# front_end_test_harness.net
KiCad netlist of a schematic drawn in EAGLE
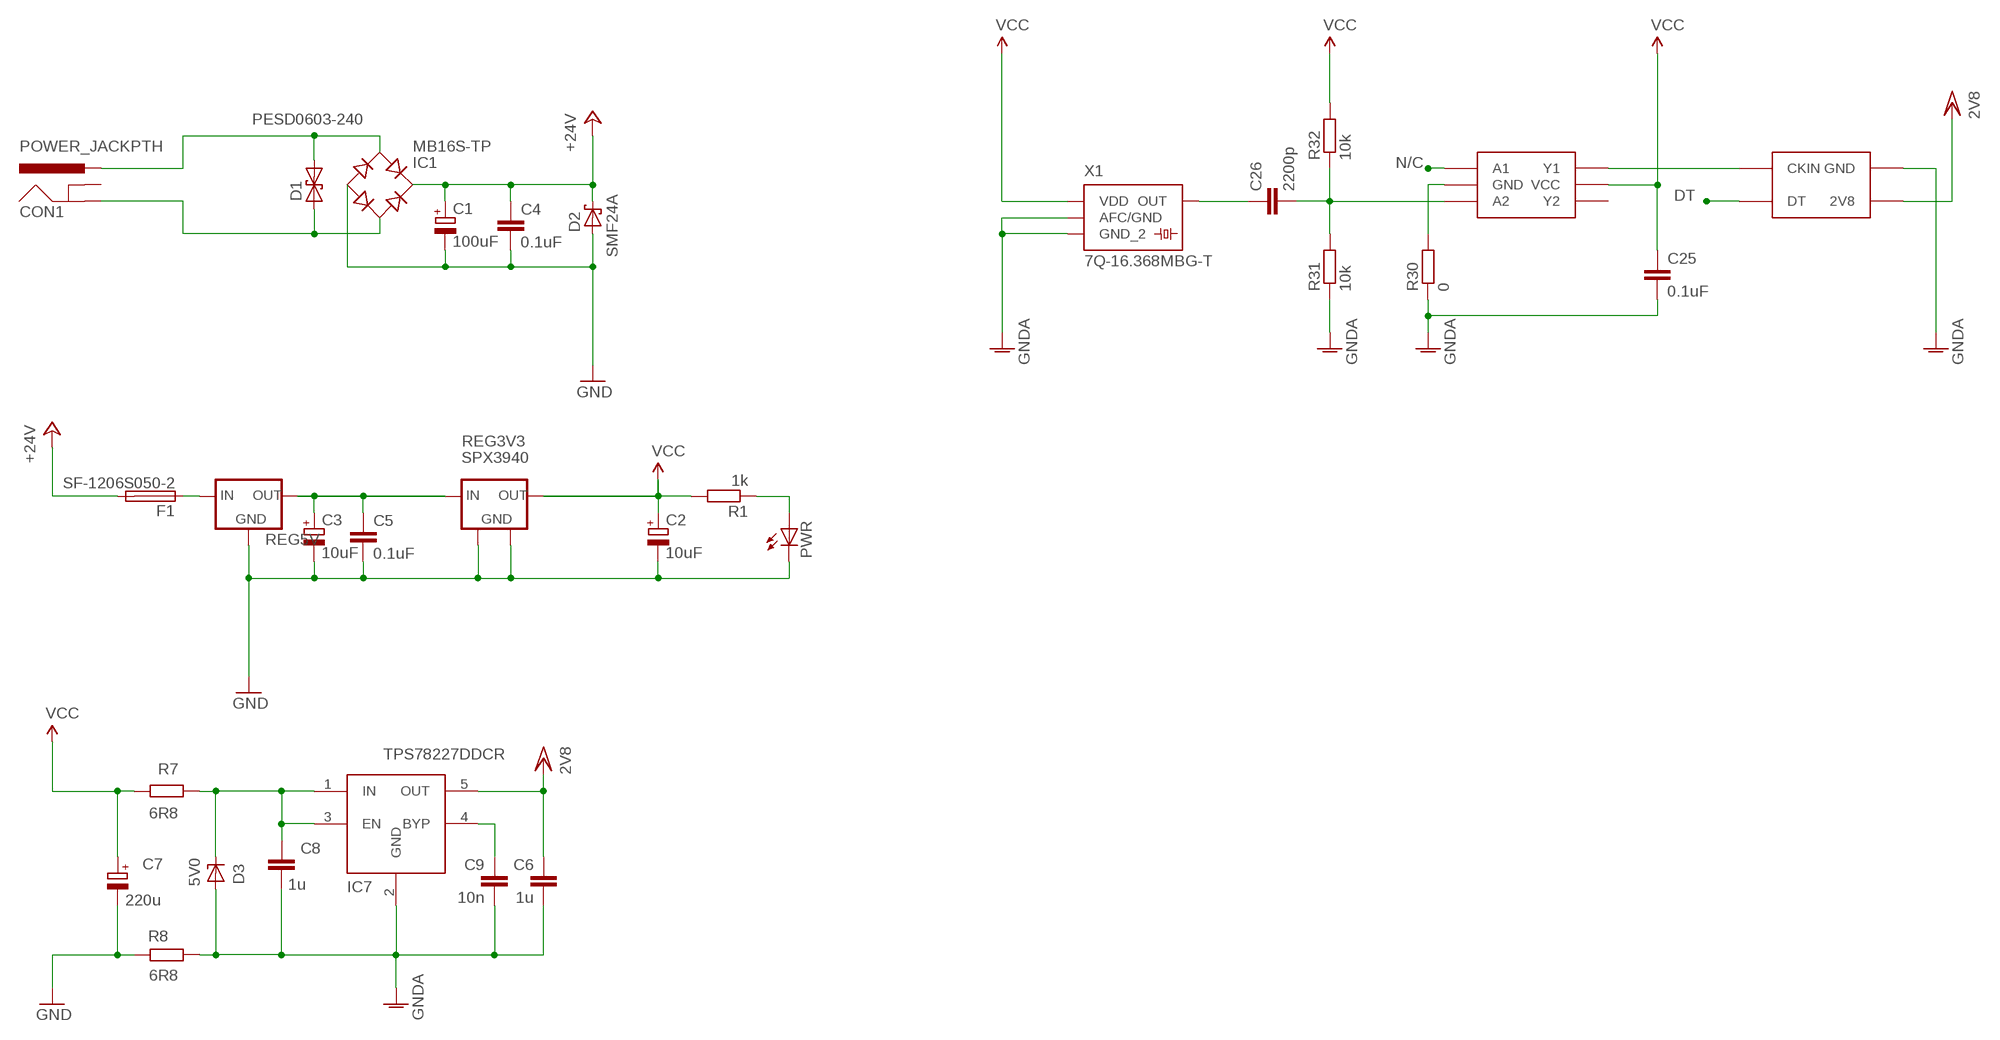
[diagram p0: schematic, sheet 1]

(export (version "E")
  (design (tool "Eeschema 10.0.6"))
  (components
    (comp (ref "C1")
      (value "100uF")
      (footprint "eagle-import:E5-10,5")
      (libsource (lib "eagle-import") (part "CPOL-EUE5-10.5"))
    )
    (comp (ref "C2")
      (value "10uF")
      (footprint "eagle-import:E2-5")
      (libsource (lib "eagle-import") (part "CPOL-EUE2-5"))
    )
    (comp (ref "C3")
      (value "10uF")
      (footprint "eagle-import:E5-10,5")
      (libsource (lib "eagle-import") (part "CPOL-EUE5-10.5"))
    )
    (comp (ref "C4")
      (value "0.1uF")
      (footprint "eagle-import:C0805")
      (libsource (lib "eagle-import") (part "C-EUC0805"))
    )
    (comp (ref "C5")
      (value "0.1uF")
      (footprint "eagle-import:C0805")
      (libsource (lib "eagle-import") (part "C-EUC0805"))
    )
    (comp (ref "C6")
      (value "1u")
      (footprint "eagle-import:C0603")
      (libsource (lib "eagle-import") (part "C-EUC0603"))
    )
    (comp (ref "C7")
      (value "220u")
      (footprint "eagle-import:C1210")
      (libsource (lib "eagle-import") (part "CPOL-EU1210"))
    )
    (comp (ref "C8")
      (value "1u")
      (footprint "eagle-import:C0603")
      (libsource (lib "eagle-import") (part "C-EUC0603"))
    )
    (comp (ref "C9")
      (value "10n")
      (footprint "eagle-import:C0603")
      (libsource (lib "eagle-import") (part "C-EUC0603"))
    )
    (comp (ref "C25")
      (value "0.1uF")
      (footprint "eagle-import:C0603")
      (libsource (lib "eagle-import") (part "C-EUC0603"))
    )
    (comp (ref "C26")
      (value "2200p")
      (footprint "eagle-import:C0603")
      (libsource (lib "eagle-import") (part "C-EUC0603"))
    )
    (comp (ref "CON1")
      (value "POWER_JACKPTH")
      (footprint "eagle-import:POWER_JACK_PTH")
      (libsource (lib "eagle-import") (part "POWER_JACKPTH"))
    )
    (comp (ref "D1")
      (value "PESD0603-240")
      (footprint "eagle-import:D0603")
      (libsource (lib "eagle-import") (part "PESD0603-240"))
    )
    (comp (ref "D2")
      (value "SMF24A")
      (footprint "eagle-import:SOD123")
      (libsource (lib "eagle-import") (part "SMF24A"))
    )
    (comp (ref "D3")
      (value "5V0")
      (footprint "eagle-import:SOD523")
      (libsource (lib "eagle-import") (part "ZENER-DIODESOD523"))
    )
    (comp (ref "F1")
      (value "SF-1206S050-2")
      (footprint "eagle-import:F1206")
      (libsource (lib "eagle-import") (part "SF-1206S050-2"))
    )
    (comp (ref "IC1")
      (value "MB16S-TP")
      (footprint "eagle-import:SOIC-4")
      (libsource (lib "eagle-import") (part "MB16S-TP"))
    )
    (comp (ref "IC7")
      (value "TPS78227DDCR")
      (footprint "eagle-import:SOT23-5")
      (libsource (lib "eagle-import") (part "NCP700BSN"))
    )
    (comp (ref "IC26")
      (value "NC7WZ16P6X")
      (footprint "eagle-import:NC7WZ16P6X")
      (libsource (lib "eagle-import") (part "NC7WZ16P6X"))
    )
    (comp (ref "PWR")
      (value "LEDCHIPLED_0805")
      (footprint "eagle-import:CHIPLED_0805")
      (libsource (lib "eagle-import") (part "LEDCHIPLED_0805"))
    )
    (comp (ref "R1")
      (value "1k")
      (footprint "eagle-import:R0603")
      (libsource (lib "eagle-import") (part "R-EU_R0603"))
    )
    (comp (ref "R7")
      (value "6R8")
      (footprint "eagle-import:R0805")
      (libsource (lib "eagle-import") (part "R-EU_R0805"))
    )
    (comp (ref "R8")
      (value "6R8")
      (footprint "eagle-import:R0805")
      (libsource (lib "eagle-import") (part "R-EU_R0805"))
    )
    (comp (ref "R30")
      (value "0")
      (footprint "eagle-import:R0603")
      (libsource (lib "eagle-import") (part "R-EU_R0603"))
    )
    (comp (ref "R31")
      (value "10k")
      (footprint "eagle-import:R0603")
      (libsource (lib "eagle-import") (part "R-EU_R0603"))
    )
    (comp (ref "R32")
      (value "10k")
      (footprint "eagle-import:R0603")
      (libsource (lib "eagle-import") (part "R-EU_R0603"))
    )
    (comp (ref "REG3V3")
      (value "SPX3940")
      (footprint "eagle-import:SOT223")
      (libsource (lib "eagle-import") (part "SPX3940"))
    )
    (comp (ref "REG5V")
      (value "V_REG_OKI-78SRSINK")
      (footprint "eagle-import:TO220-IGO")
      (libsource (lib "eagle-import") (part "V_REG_OKI-78SRSINK"))
    )
    (comp (ref "U$2")
      (value "TEST_HARNESS")
      (footprint "eagle-import:TEST_HARNESS")
      (libsource (lib "eagle-import") (part "TEST_HARNESS"))
    )
    (comp (ref "X1")
      (value "7Q-16.368MBG-T")
      (footprint "eagle-import:4-SMD")
      (libsource (lib "eagle-import") (part "7Q-16.368MBG-T"))
    )
  )
  (nets
    (net (code "1") (name "+24V") (class "Default")
      (node (ref "C1") (pin "+") (pinfunction "+_+") (pintype "passive"))
      (node (ref "C4") (pin "1") (pinfunction "1_1") (pintype "passive"))
      (node (ref "D2") (pin "C") (pinfunction "C_C") (pintype "passive"))
      (node (ref "F1") (pin "2") (pinfunction "2_2") (pintype "passive"))
      (node (ref "IC1") (pin "+") (pinfunction "+_+") (pintype "passive"))
    )
    (net (code "2") (name "/DT") (class "Default")
      (node (ref "U$2") (pin "DT@12") (pinfunction "DT_DT@12") (pintype "output"))
    )
    (net (code "3") (name "/N{slash}C") (class "Default")
      (node (ref "IC26") (pin "P$1") (pinfunction "A1_P$1") (pintype "output"))
    )
    (net (code "4") (name "2V8") (class "Default")
      (node (ref "C6") (pin "1") (pinfunction "1_1") (pintype "passive"))
      (node (ref "IC7") (pin "5") (pinfunction "OUT_5") (pintype "power_in"))
      (node (ref "U$2") (pin "2V8@11") (pinfunction "2V8_2V8@11") (pintype "power_in"))
      (node (ref "U$2") (pin "2V8@15") (pinfunction "2V8_2V8@15") (pintype "power_in"))
      (node (ref "U$2") (pin "2V8@16") (pinfunction "2V8_2V8@16") (pintype "power_in"))
    )
    (net (code "5") (name "GND") (class "Default")
      (node (ref "C1") (pin "-") (pinfunction "-_-") (pintype "passive"))
      (node (ref "C2") (pin "-") (pinfunction "-_-") (pintype "passive"))
      (node (ref "C3") (pin "-") (pinfunction "-_-") (pintype "passive"))
      (node (ref "C4") (pin "2") (pinfunction "2_2") (pintype "passive"))
      (node (ref "C5") (pin "2") (pinfunction "2_2") (pintype "passive"))
      (node (ref "C7") (pin "2") (pinfunction "-_2") (pintype "passive"))
      (node (ref "D2") (pin "A") (pinfunction "A_A") (pintype "passive"))
      (node (ref "IC1") (pin "-") (pinfunction "-_-") (pintype "passive"))
      (node (ref "PWR") (pin "C") (pinfunction "C_C") (pintype "passive"))
      (node (ref "R8") (pin "2") (pinfunction "2_2") (pintype "passive"))
      (node (ref "REG3V3") (pin "2") (pinfunction "GND_2") (pintype "power_in"))
      (node (ref "REG3V3") (pin "4") (pinfunction "GND_4") (pintype "power_in"))
      (node (ref "REG5V") (pin "GND") (pinfunction "GND_GND") (pintype "input"))
    )
    (net (code "6") (name "GNDA") (class "Default")
      (node (ref "C25") (pin "2") (pinfunction "2_2") (pintype "passive"))
      (node (ref "C6") (pin "2") (pinfunction "2_2") (pintype "passive"))
      (node (ref "C8") (pin "2") (pinfunction "2_2") (pintype "passive"))
      (node (ref "C9") (pin "2") (pinfunction "2_2") (pintype "passive"))
      (node (ref "D3") (pin "A") (pinfunction "A_A") (pintype "passive"))
      (node (ref "IC7") (pin "2") (pinfunction "GND_2") (pintype "power_in"))
      (node (ref "R30") (pin "1") (pinfunction "1_1") (pintype "passive"))
      (node (ref "R31") (pin "1") (pinfunction "1_1") (pintype "passive"))
      (node (ref "R8") (pin "1") (pinfunction "1_1") (pintype "passive"))
      (node (ref "U$2") (pin "GND@1") (pinfunction "GND_GND@1") (pintype "power_in"))
      (node (ref "U$2") (pin "GND@11") (pinfunction "GND_GND@11") (pintype "power_in"))
      (node (ref "U$2") (pin "GND@14") (pinfunction "GND_GND@14") (pintype "power_in"))
      (node (ref "U$2") (pin "GND@2") (pinfunction "GND_GND@2") (pintype "power_in"))
      (node (ref "U$2") (pin "GND@3") (pinfunction "GND_GND@3") (pintype "power_in"))
      (node (ref "U$2") (pin "GND@4") (pinfunction "GND_GND@4") (pintype "power_in"))
      (node (ref "U$2") (pin "GND@5") (pinfunction "GND_GND@5") (pintype "power_in"))
      (node (ref "U$2") (pin "GND@6") (pinfunction "GND_GND@6") (pintype "power_in"))
      (node (ref "U$2") (pin "GND@7") (pinfunction "GND_GND@7") (pintype "power_in"))
      (node (ref "U$2") (pin "GND@8") (pinfunction "GND_GND@8") (pintype "power_in"))
      (node (ref "U$2") (pin "GND@9") (pinfunction "GND_GND@9") (pintype "power_in"))
      (node (ref "X1") (pin "PAD_1") (pinfunction "AFC/GND_PAD_1") (pintype "power_in"))
      (node (ref "X1") (pin "PAD_2") (pinfunction "GND_2_PAD_2") (pintype "power_in"))
    )
    (net (code "7") (name "Net-(F1-Pad1)") (class "Default")
      (node (ref "F1") (pin "1") (pinfunction "1_1") (pintype "passive"))
      (node (ref "REG5V") (pin "IN") (pinfunction "IN_IN") (pintype "input"))
    )
    (net (code "8") (name "Net-(IC1-AC1)") (class "Default")
      (node (ref "CON1") (pin "PWR") (pinfunction "PWR_PWR") (pintype "bidirectional"))
      (node (ref "D1") (pin "2") (pinfunction "2_2") (pintype "passive"))
      (node (ref "IC1") (pin "~1") (pinfunction "AC1_~1") (pintype "passive"))
    )
    (net (code "9") (name "Net-(IC1-AC2)") (class "Default")
      (node (ref "CON1") (pin "GND") (pinfunction "GND_GND") (pintype "bidirectional"))
      (node (ref "D1") (pin "1") (pinfunction "1_1") (pintype "passive"))
      (node (ref "IC1") (pin "~2") (pinfunction "AC2_~2") (pintype "passive"))
    )
    (net (code "10") (name "Net-(IC7-BYP)") (class "Default")
      (node (ref "C9") (pin "1") (pinfunction "1_1") (pintype "passive"))
      (node (ref "IC7") (pin "4") (pinfunction "BYP_4") (pintype "bidirectional"))
    )
    (net (code "11") (name "Net-(IC7-EN)") (class "Default")
      (node (ref "C8") (pin "1") (pinfunction "1_1") (pintype "passive"))
      (node (ref "D3") (pin "C") (pinfunction "C_C") (pintype "passive"))
      (node (ref "IC7") (pin "1") (pinfunction "IN_1") (pintype "power_in"))
      (node (ref "IC7") (pin "3") (pinfunction "EN_3") (pintype "input"))
      (node (ref "R7") (pin "1") (pinfunction "1_1") (pintype "passive"))
    )
    (net (code "12") (name "Net-(IC26-A2)") (class "Default")
      (node (ref "C26") (pin "2") (pinfunction "2_2") (pintype "passive"))
      (node (ref "IC26") (pin "P$3") (pinfunction "A2_P$3") (pintype "output"))
      (node (ref "R31") (pin "2") (pinfunction "2_2") (pintype "passive"))
      (node (ref "R32") (pin "1") (pinfunction "1_1") (pintype "passive"))
    )
    (net (code "13") (name "Net-(IC26-GND)") (class "Default")
      (node (ref "IC26") (pin "P$2") (pinfunction "GND_P$2") (pintype "power_in"))
      (node (ref "R30") (pin "2") (pinfunction "2_2") (pintype "passive"))
    )
    (net (code "14") (name "Net-(IC26-Y1)") (class "Default")
      (node (ref "IC26") (pin "P$6") (pinfunction "Y1_P$6") (pintype "input"))
      (node (ref "U$2") (pin "CKIN@13") (pinfunction "CKIN_CKIN@13") (pintype "input"))
    )
    (net (code "15") (name "Net-(PWR-PadA)") (class "Default")
      (node (ref "PWR") (pin "A") (pinfunction "A_A") (pintype "passive"))
      (node (ref "R1") (pin "1") (pinfunction "1_1") (pintype "passive"))
    )
    (net (code "16") (name "Net-(REG3V3-IN)") (class "Default")
      (node (ref "C3") (pin "+") (pinfunction "+_+") (pintype "passive"))
      (node (ref "C5") (pin "1") (pinfunction "1_1") (pintype "passive"))
      (node (ref "REG3V3") (pin "1") (pinfunction "IN_1") (pintype "power_in"))
      (node (ref "REG5V") (pin "OUT") (pinfunction "OUT_OUT") (pintype "output"))
    )
    (net (code "17") (name "Net-(X1-OUT)") (class "Default")
      (node (ref "C26") (pin "1") (pinfunction "1_1") (pintype "passive"))
      (node (ref "X1") (pin "PAD_3") (pinfunction "OUT_PAD_3") (pintype "output"))
    )
    (net (code "18") (name "VCC") (class "Default")
      (node (ref "C2") (pin "+") (pinfunction "+_+") (pintype "passive"))
      (node (ref "C25") (pin "1") (pinfunction "1_1") (pintype "passive"))
      (node (ref "C7") (pin "1") (pinfunction "+_1") (pintype "passive"))
      (node (ref "IC26") (pin "P$5") (pinfunction "VCC_P$5") (pintype "power_in"))
      (node (ref "R1") (pin "2") (pinfunction "2_2") (pintype "passive"))
      (node (ref "R32") (pin "2") (pinfunction "2_2") (pintype "passive"))
      (node (ref "R7") (pin "2") (pinfunction "2_2") (pintype "passive"))
      (node (ref "REG3V3") (pin "3") (pinfunction "OUT_3") (pintype "power_in"))
      (node (ref "X1") (pin "PAD_4") (pinfunction "VDD_PAD_4") (pintype "power_in"))
    )
    (net (code "19") (name "unconnected-(CON1-PadGNDBREAK)") (class "Default")
      (node (ref "CON1") (pin "GNDBREAK") (pinfunction "GNDBREAK_GNDBREAK") (pintype "bidirectional"))
    )
    (net (code "20") (name "unconnected-(IC26-Y2-PadP$4)") (class "Default")
      (node (ref "IC26") (pin "P$4") (pinfunction "Y2_P$4") (pintype "input"))
    )
  )
)
